# MAPLE_CDH_Cntrlr.net
KiCad netlist of a schematic drawn in Altium Designer
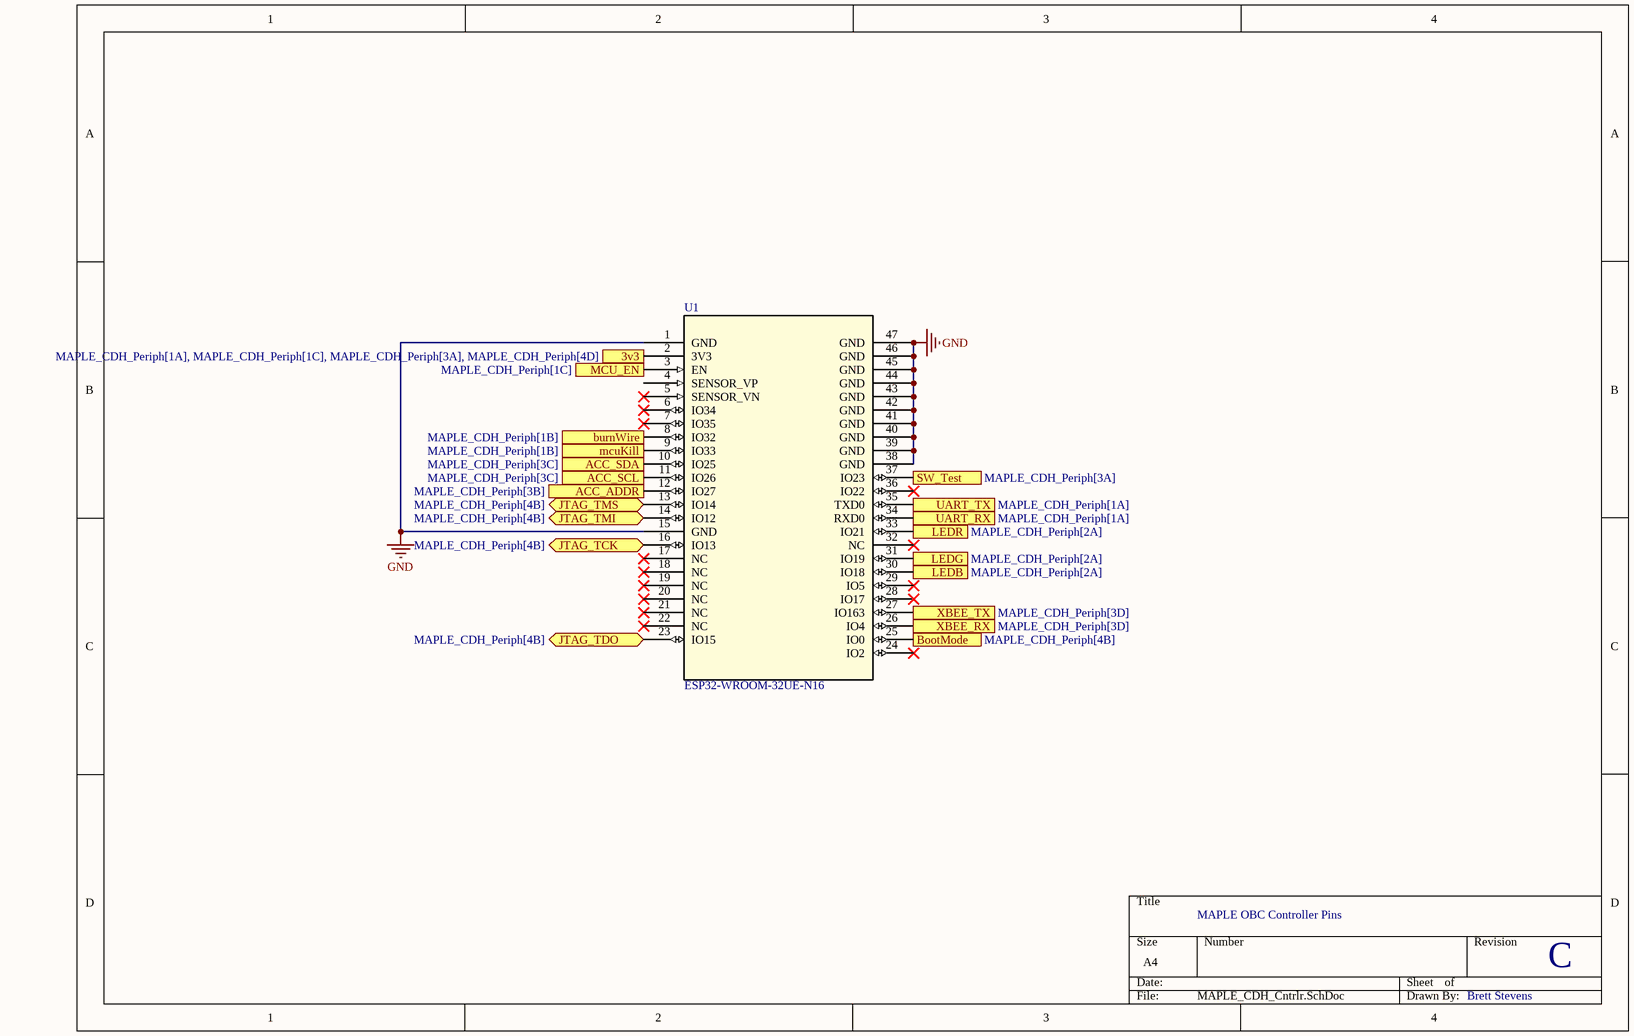
[diagram p0: MAPLE_CDH_Cntrlr.SchDoc]

(export (version "E")
  (design (tool "Eeschema 10.0.6"))
  (components
    (comp (ref "U1")
      (value "ESP32-WROOM-32UE-N16")
      (footprint "ESP32-32UE_EXP")
      (description "No Description Available")
      (fields (field (name "COPYRIGHT") "Copyright (C) 2023 Ultra Librarian. All rights reserved."))
      (libsource (lib "ESP32-WROOM-32UE-N16") (part "ESP32-WROOM-32UE-N16"))
    )
  )
  (nets
    (net (code "1") (name "/3v3") (class "Default")
      (node (ref "U1") (pin "2") (pinfunction "3V3_2") (pintype "power_in"))
    )
    (net (code "2") (name "/ACC_ADDR") (class "Default")
      (node (ref "U1") (pin "12") (pinfunction "IO27_12") (pintype "bidirectional"))
    )
    (net (code "3") (name "/ACC_SCL") (class "Default")
      (node (ref "U1") (pin "11") (pinfunction "IO26_11") (pintype "bidirectional"))
    )
    (net (code "4") (name "/ACC_SDA") (class "Default")
      (node (ref "U1") (pin "10") (pinfunction "IO25_10") (pintype "bidirectional"))
    )
    (net (code "5") (name "/BootMode") (class "Default")
      (node (ref "U1") (pin "25") (pinfunction "IO0_25") (pintype "bidirectional"))
    )
    (net (code "6") (name "/JTAG_TCK") (class "Default")
      (node (ref "U1") (pin "16") (pinfunction "IO13_16") (pintype "bidirectional"))
    )
    (net (code "7") (name "/JTAG_TDO") (class "Default")
      (node (ref "U1") (pin "23") (pinfunction "IO15_23") (pintype "bidirectional"))
    )
    (net (code "8") (name "/JTAG_TMI") (class "Default")
      (node (ref "U1") (pin "14") (pinfunction "IO12_14") (pintype "bidirectional"))
    )
    (net (code "9") (name "/JTAG_TMS") (class "Default")
      (node (ref "U1") (pin "13") (pinfunction "IO14_13") (pintype "bidirectional"))
    )
    (net (code "10") (name "/LEDB") (class "Default")
      (node (ref "U1") (pin "30") (pinfunction "IO18_30") (pintype "bidirectional"))
    )
    (net (code "11") (name "/LEDG") (class "Default")
      (node (ref "U1") (pin "31") (pinfunction "IO19_31") (pintype "bidirectional"))
    )
    (net (code "12") (name "/LEDR") (class "Default")
      (node (ref "U1") (pin "33") (pinfunction "IO21_33") (pintype "bidirectional"))
    )
    (net (code "13") (name "/MCU_EN") (class "Default")
      (node (ref "U1") (pin "3") (pinfunction "EN_3") (pintype "input"))
    )
    (net (code "14") (name "/SW_Test") (class "Default")
      (node (ref "U1") (pin "37") (pinfunction "IO23_37") (pintype "bidirectional"))
    )
    (net (code "15") (name "/UART_RX") (class "Default")
      (node (ref "U1") (pin "34") (pinfunction "RXD0_34") (pintype "bidirectional"))
    )
    (net (code "16") (name "/UART_TX") (class "Default")
      (node (ref "U1") (pin "35") (pinfunction "TXD0_35") (pintype "bidirectional"))
    )
    (net (code "17") (name "/XBEE_RX") (class "Default")
      (node (ref "U1") (pin "26") (pinfunction "IO4_26") (pintype "bidirectional"))
    )
    (net (code "18") (name "/XBEE_TX") (class "Default")
      (node (ref "U1") (pin "27") (pinfunction "IO163_27") (pintype "bidirectional"))
    )
    (net (code "19") (name "/burnWire") (class "Default")
      (node (ref "U1") (pin "8") (pinfunction "IO32_8") (pintype "bidirectional"))
    )
    (net (code "20") (name "/mcuKill") (class "Default")
      (node (ref "U1") (pin "9") (pinfunction "IO33_9") (pintype "bidirectional"))
    )
    (net (code "21") (name "GND") (class "Default")
      (node (ref "U1") (pin "1") (pinfunction "GND_1") (pintype "power_in"))
      (node (ref "U1") (pin "15") (pinfunction "GND_15") (pintype "power_in"))
      (node (ref "U1") (pin "38") (pinfunction "GND_38") (pintype "power_in"))
      (node (ref "U1") (pin "39") (pinfunction "GND_39") (pintype "power_in"))
      (node (ref "U1") (pin "40") (pinfunction "GND_40") (pintype "power_in"))
      (node (ref "U1") (pin "41") (pinfunction "GND_41") (pintype "power_in"))
      (node (ref "U1") (pin "42") (pinfunction "GND_42") (pintype "power_in"))
      (node (ref "U1") (pin "43") (pinfunction "GND_43") (pintype "power_in"))
      (node (ref "U1") (pin "44") (pinfunction "GND_44") (pintype "power_in"))
      (node (ref "U1") (pin "45") (pinfunction "GND_45") (pintype "power_in"))
      (node (ref "U1") (pin "46") (pinfunction "GND_46") (pintype "power_in"))
      (node (ref "U1") (pin "47") (pinfunction "GND_47") (pintype "power_in"))
    )
    (net (code "22") (name "unconnected-(U1-IO2-Pad24)") (class "Default")
      (node (ref "U1") (pin "24") (pinfunction "IO2_24") (pintype "bidirectional+no_connect"))
    )
    (net (code "23") (name "unconnected-(U1-IO5-Pad29)") (class "Default")
      (node (ref "U1") (pin "29") (pinfunction "IO5_29") (pintype "bidirectional+no_connect"))
    )
    (net (code "24") (name "unconnected-(U1-IO17-Pad28)") (class "Default")
      (node (ref "U1") (pin "28") (pinfunction "IO17_28") (pintype "bidirectional+no_connect"))
    )
    (net (code "25") (name "unconnected-(U1-IO22-Pad36)") (class "Default")
      (node (ref "U1") (pin "36") (pinfunction "IO22_36") (pintype "bidirectional+no_connect"))
    )
    (net (code "26") (name "unconnected-(U1-IO34-Pad6)") (class "Default")
      (node (ref "U1") (pin "6") (pinfunction "IO34_6") (pintype "bidirectional+no_connect"))
    )
    (net (code "27") (name "unconnected-(U1-IO35-Pad7)") (class "Default")
      (node (ref "U1") (pin "7") (pinfunction "IO35_7") (pintype "bidirectional+no_connect"))
    )
    (net (code "28") (name "unconnected-(U1-NC-Pad17)") (class "Default")
      (node (ref "U1") (pin "17") (pinfunction "NC_17") (pintype "passive+no_connect"))
    )
    (net (code "29") (name "unconnected-(U1-NC-Pad18)") (class "Default")
      (node (ref "U1") (pin "18") (pinfunction "NC_18") (pintype "passive+no_connect"))
    )
    (net (code "30") (name "unconnected-(U1-NC-Pad19)") (class "Default")
      (node (ref "U1") (pin "19") (pinfunction "NC_19") (pintype "passive+no_connect"))
    )
    (net (code "31") (name "unconnected-(U1-NC-Pad20)") (class "Default")
      (node (ref "U1") (pin "20") (pinfunction "NC_20") (pintype "passive+no_connect"))
    )
    (net (code "32") (name "unconnected-(U1-NC-Pad21)") (class "Default")
      (node (ref "U1") (pin "21") (pinfunction "NC_21") (pintype "passive+no_connect"))
    )
    (net (code "33") (name "unconnected-(U1-NC-Pad22)") (class "Default")
      (node (ref "U1") (pin "22") (pinfunction "NC_22") (pintype "passive+no_connect"))
    )
    (net (code "34") (name "unconnected-(U1-NC-Pad32)") (class "Default")
      (node (ref "U1") (pin "32") (pinfunction "NC_32") (pintype "passive+no_connect"))
    )
    (net (code "35") (name "unconnected-(U1-SENSOR_VN-Pad5)") (class "Default")
      (node (ref "U1") (pin "5") (pinfunction "SENSOR_VN_5") (pintype "input+no_connect"))
    )
    (net (code "36") (name "unconnected-(U1-SENSOR_VP-Pad4)") (class "Default")
      (node (ref "U1") (pin "4") (pinfunction "SENSOR_VP_4") (pintype "input"))
    )
  )
)
